# STM32.net
KiCad netlist of a schematic drawn in Altium Designer
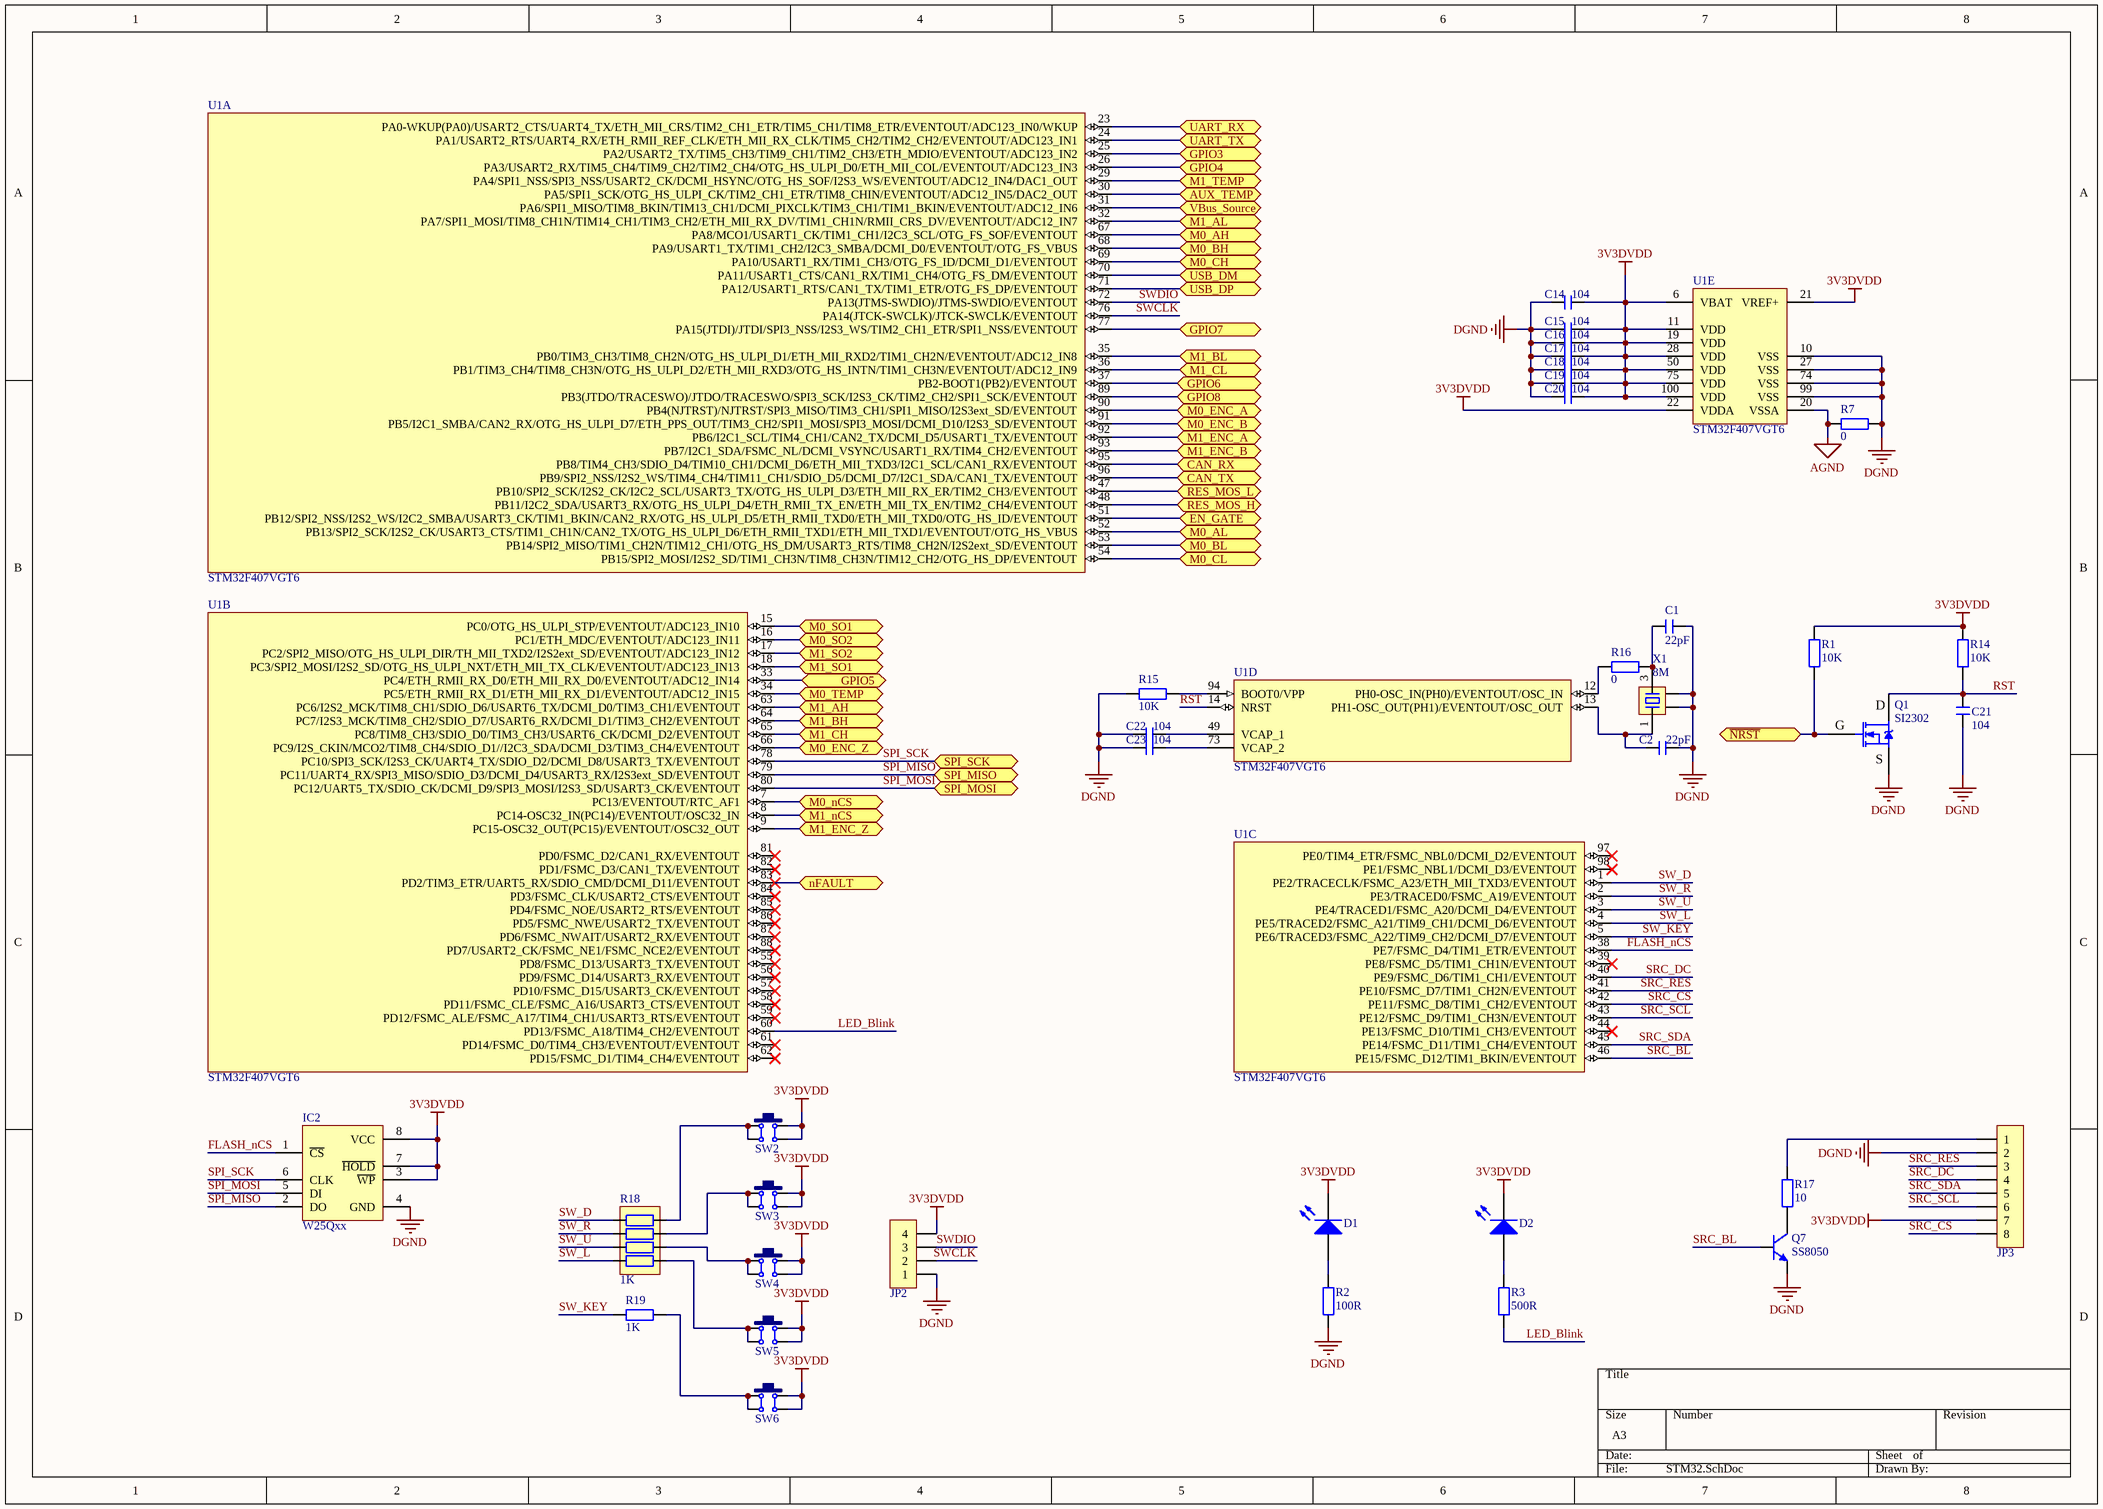
[diagram p0: STM32.SchDoc]

(export (version "E")
  (design (tool "Eeschema 10.0.6"))
  (components
    (comp (ref "C1")
      (value "22pF")
      (footprint "C 0603_L")
      (description "贴片电容")
      (libsource (lib "0.1 - 电阻-电容-电感") (part "C"))
    )
    (comp (ref "C2")
      (value "22pF")
      (footprint "C 0603_L")
      (description "贴片电容")
      (libsource (lib "0.1 - 电阻-电容-电感") (part "C"))
    )
    (comp (ref "C14")
      (value "104")
      (footprint "C 0603_L")
      (description "贴片电容")
      (libsource (lib "0.1 - 电阻-电容-电感") (part "C"))
    )
    (comp (ref "C15")
      (value "104")
      (footprint "C 0603_L")
      (description "贴片电容")
      (libsource (lib "0.1 - 电阻-电容-电感") (part "C"))
    )
    (comp (ref "C16")
      (value "104")
      (footprint "C 0603_L")
      (description "贴片电容")
      (libsource (lib "0.1 - 电阻-电容-电感") (part "C"))
    )
    (comp (ref "C17")
      (value "104")
      (footprint "C 0603_L")
      (description "贴片电容")
      (libsource (lib "0.1 - 电阻-电容-电感") (part "C"))
    )
    (comp (ref "C18")
      (value "104")
      (footprint "C 0603_L")
      (description "贴片电容")
      (libsource (lib "0.1 - 电阻-电容-电感") (part "C"))
    )
    (comp (ref "C19")
      (value "104")
      (footprint "C 0603_L")
      (description "贴片电容")
      (libsource (lib "0.1 - 电阻-电容-电感") (part "C"))
    )
    (comp (ref "C20")
      (value "104")
      (footprint "C 0603_L")
      (description "贴片电容")
      (libsource (lib "0.1 - 电阻-电容-电感") (part "C"))
    )
    (comp (ref "C21")
      (value "104")
      (footprint "C 0603_L")
      (description "贴片电容")
      (libsource (lib "0.1 - 电阻-电容-电感") (part "C"))
    )
    (comp (ref "C22")
      (value "104")
      (footprint "C 0603_L")
      (description "贴片电容")
      (libsource (lib "0.1 - 电阻-电容-电感") (part "C"))
    )
    (comp (ref "C23")
      (value "104")
      (footprint "C 0603_L")
      (description "贴片电容")
      (libsource (lib "0.1 - 电阻-电容-电感") (part "C"))
    )
    (comp (ref "D1")
      (value "LED")
      (footprint "LED 0603W")
      (description "发光二极管")
      (libsource (lib "0.3 - LED发光二极管") (part "LED"))
    )
    (comp (ref "D2")
      (value "LED")
      (footprint "LED 0603W")
      (description "发光二极管")
      (libsource (lib "0.3 - LED发光二极管") (part "LED"))
    )
    (comp (ref "IC2")
      (value "W25Qxx")
      (footprint "SOP8W_N")
      (description "SPI Flash")
      (fields (field (name "版权归属") "封装库来自淘宝 ID：黄晶宝石"))
      (libsource (lib "1.0 - 常见芯片") (part "W25Q"))
    )
    (comp (ref "JP2")
      (value "HDR-1X4")
      (footprint "HDR2.54-LI-4P")
      (description "4P接插件")
      (fields (field (name "版权归属") "封装库来自淘宝 ID：黄晶宝石"))
      (libsource (lib "5.3 - 接插件-脚距2.54 (100mil) ") (part "Header 4"))
    )
    (comp (ref "JP3")
      (value "HDR-1X8")
      (footprint "FPC0.5 2H-WS-8P")
      (description "8P接插件")
      (fields (field (name "版权归属") "封装库来自淘宝 ID：黄晶宝石"))
      (libsource (lib "5.0 - 接插件-脚距1.25") (part "Header 8"))
    )
    (comp (ref "Q1")
      (value "SI2302")
      (footprint "SOT23-3N")
      (description "N沟道场效应管")
      (libsource (lib "0.5 - 场效应管-可控硅") (part "SI2302"))
    )
    (comp (ref "Q7")
      (value "SS8050")
      (footprint "SOT23-3N")
      (description "高频放大-NPN型")
      (fields (field (name "版权归属") "封装库来自淘宝 ID：黄晶宝石"))
      (libsource (lib "0.4 - 三极管") (part "8050-SMD"))
    )
    (comp (ref "R1")
      (value "10K")
      (footprint "R 0603_L")
      (description "贴片电阻")
      (fields (field (name "版权归属") "来自淘宝 ID：黄晶宝石"))
      (libsource (lib "0.1 - 电阻-电容-电感") (part "R"))
    )
    (comp (ref "R2")
      (value "100R")
      (footprint "R 0603_L")
      (description "贴片电阻")
      (fields (field (name "版权归属") "来自淘宝 ID：黄晶宝石"))
      (libsource (lib "0.1 - 电阻-电容-电感") (part "R"))
    )
    (comp (ref "R3")
      (value "500R")
      (footprint "R 0603_L")
      (description "贴片电阻")
      (fields (field (name "版权归属") "来自淘宝 ID：黄晶宝石"))
      (libsource (lib "0.1 - 电阻-电容-电感") (part "R"))
    )
    (comp (ref "R7")
      (value "0")
      (footprint "R 0603_L")
      (description "贴片电阻")
      (fields (field (name "版权归属") "来自淘宝 ID：黄晶宝石"))
      (libsource (lib "0.1 - 电阻-电容-电感") (part "R"))
    )
    (comp (ref "R14")
      (value "10K")
      (footprint "R 0603_L")
      (description "贴片电阻")
      (fields (field (name "版权归属") "来自淘宝 ID：黄晶宝石"))
      (libsource (lib "0.1 - 电阻-电容-电感") (part "R"))
    )
    (comp (ref "R15")
      (value "10K")
      (footprint "R 0603_L")
      (description "贴片电阻")
      (fields (field (name "版权归属") "来自淘宝 ID：黄晶宝石"))
      (libsource (lib "0.1 - 电阻-电容-电感") (part "R"))
    )
    (comp (ref "R16")
      (value "0")
      (footprint "R 0603_L")
      (description "贴片电阻")
      (fields (field (name "版权归属") "来自淘宝 ID：黄晶宝石"))
      (libsource (lib "0.1 - 电阻-电容-电感") (part "R"))
    )
    (comp (ref "R17")
      (value "10")
      (footprint "R 0603_L")
      (description "贴片电阻")
      (fields (field (name "版权归属") "来自淘宝 ID：黄晶宝石"))
      (libsource (lib "0.1 - 电阻-电容-电感") (part "R"))
    )
    (comp (ref "R18")
      (value "1K")
      (footprint "RCA-8P4R-0603")
      (description "贴片排阻")
      (fields (field (name "版权归属") "封装库来自淘宝 ID：黄晶宝石"))
      (libsource (lib "0.1 - 电阻-电容-电感") (part "R-8P4R"))
    )
    (comp (ref "R19")
      (value "1K")
      (footprint "R 0603_L")
      (description "贴片电阻")
      (fields (field (name "版权归属") "来自淘宝 ID：黄晶宝石"))
      (libsource (lib "0.1 - 电阻-电容-电感") (part "R"))
    )
    (comp (ref "SW2")
      (value "6x6x5")
      (footprint "TSW SMD-6*6*4.3")
      (description "贴片6x6轻触开关")
      (fields (field (name "版权归属") "封装库来自淘宝 ID：黄晶宝石"))
      (libsource (lib "0.7 - 常用按键-开关") (part "TSW SMD-6x6"))
    )
    (comp (ref "SW3")
      (value "6x6x5")
      (footprint "TSW SMD-6*6*4.3")
      (description "贴片6x6轻触开关")
      (fields (field (name "版权归属") "封装库来自淘宝 ID：黄晶宝石"))
      (libsource (lib "0.7 - 常用按键-开关") (part "TSW SMD-6x6"))
    )
    (comp (ref "SW4")
      (value "6x6x5")
      (footprint "TSW SMD-6*6*4.3")
      (description "贴片6x6轻触开关")
      (fields (field (name "版权归属") "封装库来自淘宝 ID：黄晶宝石"))
      (libsource (lib "0.7 - 常用按键-开关") (part "TSW SMD-6x6"))
    )
    (comp (ref "SW5")
      (value "6x6x5")
      (footprint "TSW SMD-6*6*4.3")
      (description "贴片6x6轻触开关")
      (fields (field (name "版权归属") "封装库来自淘宝 ID：黄晶宝石"))
      (libsource (lib "0.7 - 常用按键-开关") (part "TSW SMD-6x6"))
    )
    (comp (ref "SW6")
      (value "6x6x5")
      (footprint "TSW SMD-6*6*4.3")
      (description "贴片6x6轻触开关")
      (fields (field (name "版权归属") "封装库来自淘宝 ID：黄晶宝石"))
      (libsource (lib "0.7 - 常用按键-开关") (part "TSW SMD-6x6"))
    )
    (comp (ref "U1")
      (value "STM32F407VGT6")
      (footprint "LQFP100_V")
      (libsource (lib "2.5 - STM32 F4系列MCU 集成库") (part "STM32F407VGT6"))
    )
    (comp (ref "X1")
      (value "8M")
      (footprint "OSC 3225-4P")
      (description "4脚无源晶振")
      (fields (field (name "版权归属") "封装库来自淘宝卖家 ID：黄晶宝石"))
      (libsource (lib "2.0 - 保险丝-晶振-光耦") (part "XTAL-4P"))
    )
  )
  (nets
    (net (code "1") (name "/AUX_TEMP") (class "Default")
      (node (ref "U1") (pin "30") (pinfunction "PA5/SPI1_SCK/OTG_HS_ULPI_CK/TIM2_CH1_ETR/TIM8_CHIN/EVENTOUT/ADC12_IN5/DAC2_OUT_30") (pintype "bidirectional"))
    )
    (net (code "2") (name "/CAN_RX") (class "Default")
      (node (ref "U1") (pin "95") (pinfunction "PB8/TIM4_CH3/SDIO_D4/TIM10_CH1/DCMI_D6/ETH_MII_TXD3/I2C1_SCL/CAN1_RX/EVENTOUT_95") (pintype "bidirectional"))
    )
    (net (code "3") (name "/CAN_TX") (class "Default")
      (node (ref "U1") (pin "96") (pinfunction "PB9/SPI2_NSS/I2S2_WS/TIM4_CH4/TIM11_CH1/SDIO_D5/DCMI_D7/I2C1_SDA/CAN1_TX/EVENTOUT_96") (pintype "bidirectional"))
    )
    (net (code "4") (name "/EN_GATE") (class "Default")
      (node (ref "U1") (pin "51") (pinfunction "PB12/SPI2_NSS/I2S2_WS/I2C2_SMBA/USART3_CK/TIM1_BKIN/CAN2_RX/OTG_HS_ULPI_D5/ETH_RMII_TXD0/ETH_MII_TXD0/OTG_HS_ID/EVENTOUT_51") (pintype "bidirectional"))
    )
    (net (code "5") (name "/FLASH_nCS") (class "Default")
      (node (ref "IC2") (pin "1") (pinfunction "~{CS}_1") (pintype "passive"))
      (node (ref "U1") (pin "38") (pinfunction "PE7/FSMC_D4/TIM1_ETR/EVENTOUT_38") (pintype "bidirectional"))
    )
    (net (code "6") (name "/GPIO3") (class "Default")
      (node (ref "U1") (pin "25") (pinfunction "PA2/USART2_TX/TIM5_CH3/TIM9_CH1/TIM2_CH3/ETH_MDIO/EVENTOUT/ADC123_IN2_25") (pintype "bidirectional"))
    )
    (net (code "7") (name "/GPIO4") (class "Default")
      (node (ref "U1") (pin "26") (pinfunction "PA3/USART2_RX/TIM5_CH4/TIM9_CH2/TIM2_CH4/OTG_HS_ULPI_D0/ETH_MII_COL/EVENTOUT/ADC123_IN3_26") (pintype "bidirectional"))
    )
    (net (code "8") (name "/GPIO5") (class "Default")
      (node (ref "U1") (pin "33") (pinfunction "PC4/ETH_RMII_RX_D0/ETH_MII_RX_D0/EVENTOUT/ADC12_IN14_33") (pintype "bidirectional"))
    )
    (net (code "9") (name "/GPIO6") (class "Default")
      (node (ref "U1") (pin "37") (pinfunction "PB2-BOOT1(PB2)/EVENTOUT_37") (pintype "bidirectional"))
    )
    (net (code "10") (name "/GPIO7") (class "Default")
      (node (ref "U1") (pin "77") (pinfunction "PA15(JTDI)/JTDI/SPI3_NSS/I2S3_WS/TIM2_CH1_ETR/SPI1_NSS/EVENTOUT_77") (pintype "bidirectional"))
    )
    (net (code "11") (name "/GPIO8") (class "Default")
      (node (ref "U1") (pin "89") (pinfunction "PB3(JTDO/TRACESWO)/JTDO/TRACESWO/SPI3_SCK/I2S3_CK/TIM2_CH2/SPI1_SCK/EVENTOUT_89") (pintype "bidirectional"))
    )
    (net (code "12") (name "/LED_Blink") (class "Default")
      (node (ref "R3") (pin "1") (pinfunction "1_1") (pintype "passive"))
      (node (ref "U1") (pin "60") (pinfunction "PD13/FSMC_A18/TIM4_CH2/EVENTOUT_60") (pintype "bidirectional"))
    )
    (net (code "13") (name "/M0_AH") (class "Default")
      (node (ref "U1") (pin "67") (pinfunction "PA8/MCO1/USART1_CK/TIM1_CH1/I2C3_SCL/OTG_FS_SOF/EVENTOUT_67") (pintype "bidirectional"))
    )
    (net (code "14") (name "/M0_AL") (class "Default")
      (node (ref "U1") (pin "52") (pinfunction "PB13/SPI2_SCK/I2S2_CK/USART3_CTS/TIM1_CH1N/CAN2_TX/OTG_HS_ULPI_D6/ETH_RMII_TXD1/ETH_MII_TXD1/EVENTOUT/OTG_HS_VBUS_52") (pintype "bidirectional"))
    )
    (net (code "15") (name "/M0_BH") (class "Default")
      (node (ref "U1") (pin "68") (pinfunction "PA9/USART1_TX/TIM1_CH2/I2C3_SMBA/DCMI_D0/EVENTOUT/OTG_FS_VBUS_68") (pintype "bidirectional"))
    )
    (net (code "16") (name "/M0_BL") (class "Default")
      (node (ref "U1") (pin "53") (pinfunction "PB14/SPI2_MISO/TIM1_CH2N/TIM12_CH1/OTG_HS_DM/USART3_RTS/TIM8_CH2N/I2S2ext_SD/EVENTOUT_53") (pintype "bidirectional"))
    )
    (net (code "17") (name "/M0_CH") (class "Default")
      (node (ref "U1") (pin "69") (pinfunction "PA10/USART1_RX/TIM1_CH3/OTG_FS_ID/DCMI_D1/EVENTOUT_69") (pintype "bidirectional"))
    )
    (net (code "18") (name "/M0_CL") (class "Default")
      (node (ref "U1") (pin "54") (pinfunction "PB15/SPI2_MOSI/I2S2_SD/TIM1_CH3N/TIM8_CH3N/TIM12_CH2/OTG_HS_DP/EVENTOUT_54") (pintype "bidirectional"))
    )
    (net (code "19") (name "/M0_ENC_A") (class "Default")
      (node (ref "U1") (pin "90") (pinfunction "PB4(NJTRST)/NJTRST/SPI3_MISO/TIM3_CH1/SPI1_MISO/I2S3ext_SD/EVENTOUT_90") (pintype "bidirectional"))
    )
    (net (code "20") (name "/M0_ENC_B") (class "Default")
      (node (ref "U1") (pin "91") (pinfunction "PB5/I2C1_SMBA/CAN2_RX/OTG_HS_ULPI_D7/ETH_PPS_OUT/TIM3_CH2/SPI1_MOSI/SPI3_MOSI/DCMI_D10/I2S3_SD/EVENTOUT_91") (pintype "bidirectional"))
    )
    (net (code "21") (name "/M0_ENC_Z") (class "Default")
      (node (ref "U1") (pin "66") (pinfunction "PC9/I2S_CKIN/MCO2/TIM8_CH4/SDIO_D1//I2C3_SDA/DCMI_D3/TIM3_CH4/EVENTOUT_66") (pintype "bidirectional"))
    )
    (net (code "22") (name "/M0_SO1") (class "Default")
      (node (ref "U1") (pin "15") (pinfunction "PC0/OTG_HS_ULPI_STP/EVENTOUT/ADC123_IN10_15") (pintype "bidirectional"))
    )
    (net (code "23") (name "/M0_SO2") (class "Default")
      (node (ref "U1") (pin "16") (pinfunction "PC1/ETH_MDC/EVENTOUT/ADC123_IN11_16") (pintype "bidirectional"))
    )
    (net (code "24") (name "/M0_TEMP") (class "Default")
      (node (ref "U1") (pin "34") (pinfunction "PC5/ETH_RMII_RX_D1/ETH_MII_RX_D1/EVENTOUT/ADC12_IN15_34") (pintype "bidirectional"))
    )
    (net (code "25") (name "/M0_nCS") (class "Default")
      (node (ref "U1") (pin "7") (pinfunction "PC13/EVENTOUT/RTC_AF1_7") (pintype "bidirectional"))
    )
    (net (code "26") (name "/M1_AH") (class "Default")
      (node (ref "U1") (pin "63") (pinfunction "PC6/I2S2_MCK/TIM8_CH1/SDIO_D6/USART6_TX/DCMI_D0/TIM3_CH1/EVENTOUT_63") (pintype "bidirectional"))
    )
    (net (code "27") (name "/M1_AL") (class "Default")
      (node (ref "U1") (pin "32") (pinfunction "PA7/SPI1_MOSI/TIM8_CH1N/TIM14_CH1/TIM3_CH2/ETH_MII_RX_DV/TIM1_CH1N/RMII_CRS_DV/EVENTOUT/ADC12_IN7_32") (pintype "bidirectional"))
    )
    (net (code "28") (name "/M1_BH") (class "Default")
      (node (ref "U1") (pin "64") (pinfunction "PC7/I2S3_MCK/TIM8_CH2/SDIO_D7/USART6_RX/DCMI_D1/TIM3_CH2/EVENTOUT_64") (pintype "bidirectional"))
    )
    (net (code "29") (name "/M1_BL") (class "Default")
      (node (ref "U1") (pin "35") (pinfunction "PB0/TIM3_CH3/TIM8_CH2N/OTG_HS_ULPI_D1/ETH_MII_RXD2/TIM1_CH2N/EVENTOUT/ADC12_IN8_35") (pintype "bidirectional"))
    )
    (net (code "30") (name "/M1_CH") (class "Default")
      (node (ref "U1") (pin "65") (pinfunction "PC8/TIM8_CH3/SDIO_D0/TIM3_CH3/USART6_CK/DCMI_D2/EVENTOUT_65") (pintype "bidirectional"))
    )
    (net (code "31") (name "/M1_CL") (class "Default")
      (node (ref "U1") (pin "36") (pinfunction "PB1/TIM3_CH4/TIM8_CH3N/OTG_HS_ULPI_D2/ETH_MII_RXD3/OTG_HS_INTN/TIM1_CH3N/EVENTOUT/ADC12_IN9_36") (pintype "bidirectional"))
    )
    (net (code "32") (name "/M1_ENC_A") (class "Default")
      (node (ref "U1") (pin "92") (pinfunction "PB6/I2C1_SCL/TIM4_CH1/CAN2_TX/DCMI_D5/USART1_TX/EVENTOUT_92") (pintype "bidirectional"))
    )
    (net (code "33") (name "/M1_ENC_B") (class "Default")
      (node (ref "U1") (pin "93") (pinfunction "PB7/I2C1_SDA/FSMC_NL/DCMI_VSYNC/USART1_RX/TIM4_CH2/EVENTOUT_93") (pintype "bidirectional"))
    )
    (net (code "34") (name "/M1_ENC_Z") (class "Default")
      (node (ref "U1") (pin "9") (pinfunction "PC15-OSC32_OUT(PC15)/EVENTOUT/OSC32_OUT_9") (pintype "bidirectional"))
    )
    (net (code "35") (name "/M1_SO1") (class "Default")
      (node (ref "U1") (pin "18") (pinfunction "PC3/SPI2_MOSI/I2S2_SD/OTG_HS_ULPI_NXT/ETH_MII_TX_CLK/EVENTOUT/ADC123_IN13_18") (pintype "bidirectional"))
    )
    (net (code "36") (name "/M1_SO2") (class "Default")
      (node (ref "U1") (pin "17") (pinfunction "PC2/SPI2_MISO/OTG_HS_ULPI_DIR/TH_MII_TXD2/I2S2ext_SD/EVENTOUT/ADC123_IN12_17") (pintype "bidirectional"))
    )
    (net (code "37") (name "/M1_TEMP") (class "Default")
      (node (ref "U1") (pin "29") (pinfunction "PA4/SPI1_NSS/SPI3_NSS/USART2_CK/DCMI_HSYNC/OTG_HS_SOF/I2S3_WS/EVENTOUT/ADC12_IN4/DAC1_OUT_29") (pintype "bidirectional"))
    )
    (net (code "38") (name "/M1_nCS") (class "Default")
      (node (ref "U1") (pin "8") (pinfunction "PC14-OSC32_IN(PC14)/EVENTOUT/OSC32_IN_8") (pintype "bidirectional"))
    )
    (net (code "39") (name "/RES_MOS_H") (class "Default")
      (node (ref "U1") (pin "48") (pinfunction "PB11/I2C2_SDA/USART3_RX/OTG_HS_ULPI_D4/ETH_RMII_TX_EN/ETH_MII_TX_EN/TIM2_CH4/EVENTOUT_48") (pintype "bidirectional"))
    )
    (net (code "40") (name "/RES_MOS_L") (class "Default")
      (node (ref "U1") (pin "47") (pinfunction "PB10/SPI2_SCK/I2S2_CK/I2C2_SCL/USART3_TX/OTG_HS_ULPI_D3/ETH_MII_RX_ER/TIM2_CH3/EVENTOUT_47") (pintype "bidirectional"))
    )
    (net (code "41") (name "/RST") (class "Default")
      (node (ref "C21") (pin "2") (pinfunction "2_2") (pintype "passive"))
      (node (ref "Q1") (pin "3") (pinfunction "D_3") (pintype "passive"))
      (node (ref "R14") (pin "1") (pinfunction "1_1") (pintype "passive"))
      (node (ref "U1") (pin "14") (pinfunction "NRST_14") (pintype "bidirectional"))
    )
    (net (code "42") (name "/SPI_MISO") (class "Default")
      (node (ref "IC2") (pin "2") (pinfunction "DO_2") (pintype "passive"))
      (node (ref "U1") (pin "79") (pinfunction "PC11/UART4_RX/SPI3_MISO/SDIO_D3/DCMI_D4/USART3_RX/I2S3ext_SD/EVENTOUT_79") (pintype "bidirectional"))
    )
    (net (code "43") (name "/SPI_MOSI") (class "Default")
      (node (ref "IC2") (pin "5") (pinfunction "DI_5") (pintype "passive"))
      (node (ref "U1") (pin "80") (pinfunction "PC12/UART5_TX/SDIO_CK/DCMI_D9/SPI3_MOSI/I2S3_SD/USART3_CK/EVENTOUT_80") (pintype "bidirectional"))
    )
    (net (code "44") (name "/SPI_SCK") (class "Default")
      (node (ref "IC2") (pin "6") (pinfunction "CLK_6") (pintype "passive"))
      (node (ref "U1") (pin "78") (pinfunction "PC10/SPI3_SCK/I2S3_CK/UART4_TX/SDIO_D2/DCMI_D8/USART3_TX/EVENTOUT_78") (pintype "bidirectional"))
    )
    (net (code "45") (name "/SRC_BL") (class "Default")
      (node (ref "Q7") (pin "1") (pinfunction "B_1") (pintype "passive"))
      (node (ref "U1") (pin "46") (pinfunction "PE15/FSMC_D12/TIM1_BKIN/EVENTOUT_46") (pintype "bidirectional"))
    )
    (net (code "46") (name "/SRC_CS") (class "Default")
      (node (ref "JP3") (pin "8") (pinfunction "8_8") (pintype "passive"))
      (node (ref "U1") (pin "42") (pinfunction "PE11/FSMC_D8/TIM1_CH2/EVENTOUT_42") (pintype "bidirectional"))
    )
    (net (code "47") (name "/SRC_DC") (class "Default")
      (node (ref "JP3") (pin "4") (pinfunction "4_4") (pintype "passive"))
      (node (ref "U1") (pin "40") (pinfunction "PE9/FSMC_D6/TIM1_CH1/EVENTOUT_40") (pintype "bidirectional"))
    )
    (net (code "48") (name "/SRC_RES") (class "Default")
      (node (ref "JP3") (pin "3") (pinfunction "3_3") (pintype "passive"))
      (node (ref "U1") (pin "41") (pinfunction "PE10/FSMC_D7/TIM1_CH2N/EVENTOUT_41") (pintype "bidirectional"))
    )
    (net (code "49") (name "/SRC_SCL") (class "Default")
      (node (ref "JP3") (pin "6") (pinfunction "6_6") (pintype "passive"))
      (node (ref "U1") (pin "43") (pinfunction "PE12/FSMC_D9/TIM1_CH3N/EVENTOUT_43") (pintype "bidirectional"))
    )
    (net (code "50") (name "/SRC_SDA") (class "Default")
      (node (ref "JP3") (pin "5") (pinfunction "5_5") (pintype "passive"))
      (node (ref "U1") (pin "45") (pinfunction "PE14/FSMC_D11/TIM1_CH4/EVENTOUT_45") (pintype "bidirectional"))
    )
    (net (code "51") (name "/SWCLK") (class "Default")
      (node (ref "JP2") (pin "2") (pinfunction "2_2") (pintype "passive"))
      (node (ref "U1") (pin "76") (pinfunction "PA14(JTCK-SWCLK)/JTCK-SWCLK/EVENTOUT_76") (pintype "bidirectional"))
    )
    (net (code "52") (name "/SWDIO") (class "Default")
      (node (ref "JP2") (pin "3") (pinfunction "3_3") (pintype "passive"))
      (node (ref "U1") (pin "72") (pinfunction "PA13(JTMS-SWDIO)/JTMS-SWDIO/EVENTOUT_72") (pintype "bidirectional"))
    )
    (net (code "53") (name "/SW_D") (class "Default")
      (node (ref "R18") (pin "8") (pinfunction "8_8") (pintype "passive"))
      (node (ref "U1") (pin "1") (pinfunction "PE2/TRACECLK/FSMC_A23/ETH_MII_TXD3/EVENTOUT_1") (pintype "bidirectional"))
    )
    (net (code "54") (name "/SW_KEY") (class "Default")
      (node (ref "R19") (pin "2") (pinfunction "2_2") (pintype "passive"))
      (node (ref "U1") (pin "5") (pinfunction "PE6/TRACED3/FSMC_A22/TIM9_CH2/DCMI_D7/EVENTOUT_5") (pintype "bidirectional"))
    )
    (net (code "55") (name "/SW_L") (class "Default")
      (node (ref "R18") (pin "5") (pinfunction "5_5") (pintype "passive"))
      (node (ref "U1") (pin "4") (pinfunction "PE5/TRACED2/FSMC_A21/TIM9_CH1/DCMI_D6/EVENTOUT_4") (pintype "bidirectional"))
    )
    (net (code "56") (name "/SW_R") (class "Default")
      (node (ref "R18") (pin "7") (pinfunction "7_7") (pintype "passive"))
      (node (ref "U1") (pin "2") (pinfunction "PE3/TRACED0/FSMC_A19/EVENTOUT_2") (pintype "bidirectional"))
    )
    (net (code "57") (name "/SW_U") (class "Default")
      (node (ref "R18") (pin "6") (pinfunction "6_6") (pintype "passive"))
      (node (ref "U1") (pin "3") (pinfunction "PE4/TRACED1/FSMC_A20/DCMI_D4/EVENTOUT_3") (pintype "bidirectional"))
    )
    (net (code "58") (name "/UART_RX") (class "Default")
      (node (ref "U1") (pin "23") (pinfunction "PA0-WKUP(PA0)/USART2_CTS/UART4_TX/ETH_MII_CRS/TIM2_CH1_ETR/TIM5_CH1/TIM8_ETR/EVENTOUT/ADC123_IN0/WKUP_23") (pintype "bidirectional"))
    )
    (net (code "59") (name "/UART_TX") (class "Default")
      (node (ref "U1") (pin "24") (pinfunction "PA1/USART2_RTS/UART4_RX/ETH_RMII_REF_CLK/ETH_MII_RX_CLK/TIM5_CH2/TIM2_CH2/EVENTOUT/ADC123_IN1_24") (pintype "bidirectional"))
    )
    (net (code "60") (name "/USB_DM") (class "Default")
      (node (ref "U1") (pin "70") (pinfunction "PA11/USART1_CTS/CAN1_RX/TIM1_CH4/OTG_FS_DM/EVENTOUT_70") (pintype "bidirectional"))
    )
    (net (code "61") (name "/USB_DP") (class "Default")
      (node (ref "U1") (pin "71") (pinfunction "PA12/USART1_RTS/CAN1_TX/TIM1_ETR/OTG_FS_DP/EVENTOUT_71") (pintype "bidirectional"))
    )
    (net (code "62") (name "/VBus_Source") (class "Default")
      (node (ref "U1") (pin "31") (pinfunction "PA6/SPI1_MISO/TIM8_BKIN/TIM13_CH1/DCMI_PIXCLK/TIM3_CH1/TIM1_BKIN/EVENTOUT/ADC12_IN6_31") (pintype "bidirectional"))
    )
    (net (code "63") (name "/nFAULT") (class "Default")
      (node (ref "U1") (pin "83") (pinfunction "PD2/TIM3_ETR/UART5_RX/SDIO_CMD/DCMI_D11/EVENTOUT_83") (pintype "bidirectional+no_connect"))
    )
    (net (code "64") (name "/~{NRST}") (class "Default")
      (node (ref "Q1") (pin "1") (pinfunction "G_1") (pintype "passive"))
      (node (ref "R1") (pin "1") (pinfunction "1_1") (pintype "passive"))
    )
    (net (code "65") (name "3V3DVDD") (class "Default")
      (node (ref "C14") (pin "2") (pinfunction "2_2") (pintype "passive"))
      (node (ref "C15") (pin "2") (pinfunction "2_2") (pintype "passive"))
      (node (ref "C16") (pin "2") (pinfunction "2_2") (pintype "passive"))
      (node (ref "C17") (pin "2") (pinfunction "2_2") (pintype "passive"))
      (node (ref "C18") (pin "2") (pinfunction "2_2") (pintype "passive"))
      (node (ref "C19") (pin "2") (pinfunction "2_2") (pintype "passive"))
      (node (ref "C20") (pin "2") (pinfunction "2_2") (pintype "passive"))
      (node (ref "D1") (pin "2") (pinfunction "K_2") (pintype "passive"))
      (node (ref "D2") (pin "2") (pinfunction "K_2") (pintype "passive"))
      (node (ref "IC2") (pin "3") (pinfunction "~{WP}_3") (pintype "passive"))
      (node (ref "IC2") (pin "7") (pinfunction "~{HOLD}_7") (pintype "passive"))
      (node (ref "IC2") (pin "8") (pinfunction "VCC_8") (pintype "passive"))
      (node (ref "JP2") (pin "4") (pinfunction "4_4") (pintype "passive"))
      (node (ref "JP3") (pin "7") (pinfunction "7_7") (pintype "passive"))
      (node (ref "R1") (pin "2") (pinfunction "2_2") (pintype "passive"))
      (node (ref "R14") (pin "2") (pinfunction "2_2") (pintype "passive"))
      (node (ref "SW2") (pin "2") (pinfunction "2_2") (pintype "passive"))
      (node (ref "SW2") (pin "3") (pinfunction "3_3") (pintype "passive"))
      (node (ref "SW3") (pin "2") (pinfunction "2_2") (pintype "passive"))
      (node (ref "SW3") (pin "3") (pinfunction "3_3") (pintype "passive"))
      (node (ref "SW4") (pin "2") (pinfunction "2_2") (pintype "passive"))
      (node (ref "SW4") (pin "3") (pinfunction "3_3") (pintype "passive"))
      (node (ref "SW5") (pin "2") (pinfunction "2_2") (pintype "passive"))
      (node (ref "SW5") (pin "3") (pinfunction "3_3") (pintype "passive"))
      (node (ref "SW6") (pin "2") (pinfunction "2_2") (pintype "passive"))
      (node (ref "SW6") (pin "3") (pinfunction "3_3") (pintype "passive"))
      (node (ref "U1") (pin "100") (pinfunction "VDD_100") (pintype "power_in"))
      (node (ref "U1") (pin "11") (pinfunction "VDD_11") (pintype "power_in"))
      (node (ref "U1") (pin "19") (pinfunction "VDD_19") (pintype "power_in"))
      (node (ref "U1") (pin "21") (pinfunction "VREF+_21") (pintype "power_in"))
      (node (ref "U1") (pin "22") (pinfunction "VDDA_22") (pintype "power_in"))
      (node (ref "U1") (pin "28") (pinfunction "VDD_28") (pintype "power_in"))
      (node (ref "U1") (pin "50") (pinfunction "VDD_50") (pintype "power_in"))
      (node (ref "U1") (pin "6") (pinfunction "VBAT_6") (pintype "power_in"))
      (node (ref "U1") (pin "75") (pinfunction "VDD_75") (pintype "power_in"))
    )
    (net (code "66") (name "AGND") (class "Default")
      (node (ref "R7") (pin "2") (pinfunction "2_2") (pintype "passive"))
      (node (ref "U1") (pin "20") (pinfunction "VSSA_20") (pintype "power_in"))
    )
    (net (code "67") (name "DGND") (class "Default")
      (node (ref "C1") (pin "1") (pinfunction "1_1") (pintype "passive"))
      (node (ref "C14") (pin "1") (pinfunction "1_1") (pintype "passive"))
      (node (ref "C15") (pin "1") (pinfunction "1_1") (pintype "passive"))
      (node (ref "C16") (pin "1") (pinfunction "1_1") (pintype "passive"))
      (node (ref "C17") (pin "1") (pinfunction "1_1") (pintype "passive"))
      (node (ref "C18") (pin "1") (pinfunction "1_1") (pintype "passive"))
      (node (ref "C19") (pin "1") (pinfunction "1_1") (pintype "passive"))
      (node (ref "C2") (pin "2") (pinfunction "2_2") (pintype "passive"))
      (node (ref "C20") (pin "1") (pinfunction "1_1") (pintype "passive"))
      (node (ref "C21") (pin "1") (pinfunction "1_1") (pintype "passive"))
      (node (ref "C22") (pin "1") (pinfunction "1_1") (pintype "passive"))
      (node (ref "C23") (pin "1") (pinfunction "1_1") (pintype "passive"))
      (node (ref "IC2") (pin "4") (pinfunction "GND_4") (pintype "passive"))
      (node (ref "JP2") (pin "1") (pinfunction "1_1") (pintype "passive"))
      (node (ref "JP3") (pin "2") (pinfunction "2_2") (pintype "passive"))
      (node (ref "Q1") (pin "2") (pinfunction "S_2") (pintype "passive"))
      (node (ref "Q7") (pin "2") (pinfunction "E_2") (pintype "passive"))
      (node (ref "R15") (pin "1") (pinfunction "1_1") (pintype "passive"))
      (node (ref "R2") (pin "1") (pinfunction "1_1") (pintype "passive"))
      (node (ref "R7") (pin "1") (pinfunction "1_1") (pintype "passive"))
      (node (ref "U1") (pin "10") (pinfunction "VSS_10") (pintype "power_in"))
      (node (ref "U1") (pin "27") (pinfunction "VSS_27") (pintype "power_in"))
      (node (ref "U1") (pin "74") (pinfunction "VSS_74") (pintype "power_in"))
      (node (ref "U1") (pin "99") (pinfunction "VSS_99") (pintype "power_in"))
      (node (ref "X1") (pin "2") (pinfunction "2_2") (pintype "passive"))
      (node (ref "X1") (pin "4") (pinfunction "4_4") (pintype "passive"))
    )
    (net (code "68") (name "Net-(C1-Pad2)") (class "Default")
      (node (ref "C1") (pin "2") (pinfunction "2_2") (pintype "passive"))
      (node (ref "R16") (pin "1") (pinfunction "1_1") (pintype "passive"))
      (node (ref "X1") (pin "3") (pinfunction "3_3") (pintype "passive"))
    )
    (net (code "69") (name "Net-(D1-A)") (class "Default")
      (node (ref "D1") (pin "1") (pinfunction "A_1") (pintype "passive"))
      (node (ref "R2") (pin "2") (pinfunction "2_2") (pintype "passive"))
    )
    (net (code "70") (name "Net-(D2-A)") (class "Default")
      (node (ref "D2") (pin "1") (pinfunction "A_1") (pintype "passive"))
      (node (ref "R3") (pin "2") (pinfunction "2_2") (pintype "passive"))
    )
    (net (code "71") (name "Net-(JP3-Pad1)") (class "Default")
      (node (ref "JP3") (pin "1") (pinfunction "1_1") (pintype "passive"))
      (node (ref "R17") (pin "2") (pinfunction "2_2") (pintype "passive"))
    )
    (net (code "72") (name "Net-(Q7-C)") (class "Default")
      (node (ref "Q7") (pin "3") (pinfunction "C_3") (pintype "passive"))
      (node (ref "R17") (pin "1") (pinfunction "1_1") (pintype "passive"))
    )
    (net (code "73") (name "Net-(R18-Pad1)") (class "Default")
      (node (ref "R18") (pin "1") (pinfunction "1_1") (pintype "passive"))
      (node (ref "SW2") (pin "1") (pinfunction "1_1") (pintype "passive"))
      (node (ref "SW2") (pin "4") (pinfunction "4_4") (pintype "passive"))
    )
    (net (code "74") (name "Net-(R18-Pad2)") (class "Default")
      (node (ref "R18") (pin "2") (pinfunction "2_2") (pintype "passive"))
      (node (ref "SW3") (pin "1") (pinfunction "1_1") (pintype "passive"))
      (node (ref "SW3") (pin "4") (pinfunction "4_4") (pintype "passive"))
    )
    (net (code "75") (name "Net-(R18-Pad3)") (class "Default")
      (node (ref "R18") (pin "3") (pinfunction "3_3") (pintype "passive"))
      (node (ref "SW4") (pin "1") (pinfunction "1_1") (pintype "passive"))
      (node (ref "SW4") (pin "4") (pinfunction "4_4") (pintype "passive"))
    )
    (net (code "76") (name "Net-(R18-Pad4)") (class "Default")
      (node (ref "R18") (pin "4") (pinfunction "4_4") (pintype "passive"))
      (node (ref "SW5") (pin "1") (pinfunction "1_1") (pintype "passive"))
      (node (ref "SW5") (pin "4") (pinfunction "4_4") (pintype "passive"))
    )
    (net (code "77") (name "Net-(R19-Pad1)") (class "Default")
      (node (ref "R19") (pin "1") (pinfunction "1_1") (pintype "passive"))
      (node (ref "SW6") (pin "1") (pinfunction "1_1") (pintype "passive"))
      (node (ref "SW6") (pin "4") (pinfunction "4_4") (pintype "passive"))
    )
    (net (code "78") (name "Net-(U1D-BOOT0{slash}VPP)") (class "Default")
      (node (ref "R15") (pin "2") (pinfunction "2_2") (pintype "passive"))
      (node (ref "U1") (pin "94") (pinfunction "BOOT0/VPP_94") (pintype "input"))
    )
    (net (code "79") (name "Net-(U1D-PH0-OSC_IN(PH0){slash}EVENTOUT{slash}OSC_IN)") (class "Default")
      (node (ref "R16") (pin "2") (pinfunction "2_2") (pintype "passive"))
      (node (ref "U1") (pin "12") (pinfunction "PH0-OSC_IN(PH0)/EVENTOUT/OSC_IN_12") (pintype "bidirectional"))
    )
    (net (code "80") (name "Net-(U1D-PH1-OSC_OUT(PH1){slash}EVENTOUT{slash}OSC_OUT)") (class "Default")
      (node (ref "C2") (pin "1") (pinfunction "1_1") (pintype "passive"))
      (node (ref "U1") (pin "13") (pinfunction "PH1-OSC_OUT(PH1)/EVENTOUT/OSC_OUT_13") (pintype "bidirectional"))
      (node (ref "X1") (pin "1") (pinfunction "1_1") (pintype "passive"))
    )
    (net (code "81") (name "Net-(U1D-VCAP_1)") (class "Default")
      (node (ref "C22") (pin "2") (pinfunction "2_2") (pintype "passive"))
      (node (ref "U1") (pin "49") (pinfunction "VCAP_1_49") (pintype "power_in"))
    )
    (net (code "82") (name "Net-(U1D-VCAP_2)") (class "Default")
      (node (ref "C23") (pin "2") (pinfunction "2_2") (pintype "passive"))
      (node (ref "U1") (pin "73") (pinfunction "VCAP_2_73") (pintype "power_in"))
    )
    (net (code "83") (name "unconnected-(U1B-PD0{slash}FSMC_D2{slash}CAN1_RX{slash}EVENTOUT-Pad81)") (class "Default")
      (node (ref "U1") (pin "81") (pinfunction "PD0/FSMC_D2/CAN1_RX/EVENTOUT_81") (pintype "bidirectional+no_connect"))
    )
    (net (code "84") (name "unconnected-(U1B-PD1{slash}FSMC_D3{slash}CAN1_TX{slash}EVENTOUT-Pad82)") (class "Default")
      (node (ref "U1") (pin "82") (pinfunction "PD1/FSMC_D3/CAN1_TX/EVENTOUT_82") (pintype "bidirectional+no_connect"))
    )
    (net (code "85") (name "unconnected-(U1B-PD3{slash}FSMC_CLK{slash}USART2_CTS{slash}EVENTOUT-Pad84)") (class "Default")
      (node (ref "U1") (pin "84") (pinfunction "PD3/FSMC_CLK/USART2_CTS/EVENTOUT_84") (pintype "bidirectional+no_connect"))
    )
    (net (code "86") (name "unconnected-(U1B-PD4{slash}FSMC_NOE{slash}USART2_RTS{slash}EVENTOUT-Pad85)") (class "Default")
      (node (ref "U1") (pin "85") (pinfunction "PD4/FSMC_NOE/USART2_RTS/EVENTOUT_85") (pintype "bidirectional+no_connect"))
    )
    (net (code "87") (name "unconnected-(U1B-PD5{slash}FSMC_NWE{slash}USART2_TX{slash}EVENTOUT-Pad86)") (class "Default")
      (node (ref "U1") (pin "86") (pinfunction "PD5/FSMC_NWE/USART2_TX/EVENTOUT_86") (pintype "bidirectional+no_connect"))
    )
    (net (code "88") (name "unconnected-(U1B-PD6{slash}FSMC_NWAIT{slash}USART2_RX{slash}EVENTOUT-Pad87)") (class "Default")
      (node (ref "U1") (pin "87") (pinfunction "PD6/FSMC_NWAIT/USART2_RX/EVENTOUT_87") (pintype "bidirectional+no_connect"))
    )
    (net (code "89") (name "unconnected-(U1B-PD7{slash}USART2_CK{slash}FSMC_NE1{slash}FSMC_NCE2{slash}EVENTOUT-Pad88)") (class "Default")
      (node (ref "U1") (pin "88") (pinfunction "PD7/USART2_CK/FSMC_NE1/FSMC_NCE2/EVENTOUT_88") (pintype "bidirectional+no_connect"))
    )
    (net (code "90") (name "unconnected-(U1B-PD8{slash}FSMC_D13{slash}USART3_TX{slash}EVENTOUT-Pad55)") (class "Default")
      (node (ref "U1") (pin "55") (pinfunction "PD8/FSMC_D13/USART3_TX/EVENTOUT_55") (pintype "bidirectional+no_connect"))
    )
    (net (code "91") (name "unconnected-(U1B-PD9{slash}FSMC_D14{slash}USART3_RX{slash}EVENTOUT-Pad56)") (class "Default")
      (node (ref "U1") (pin "56") (pinfunction "PD9/FSMC_D14/USART3_RX/EVENTOUT_56") (pintype "bidirectional+no_connect"))
    )
    (net (code "92") (name "unconnected-(U1B-PD10{slash}FSMC_D15{slash}USART3_CK{slash}EVENTOUT-Pad57)") (class "Default")
      (node (ref "U1") (pin "57") (pinfunction "PD10/FSMC_D15/USART3_CK/EVENTOUT_57") (pintype "bidirectional+no_connect"))
    )
    (net (code "93") (name "unconnected-(U1B-PD11{slash}FSMC_CLE{slash}FSMC_A16{slash}USART3_CTS{slash}EVENTOUT-Pad58)") (class "Default")
      (node (ref "U1") (pin "58") (pinfunction "PD11/FSMC_CLE/FSMC_A16/USART3_CTS/EVENTOUT_58") (pintype "bidirectional+no_connect"))
    )
    (net (code "94") (name "unconnected-(U1B-PD12{slash}FSMC_ALE{slash}FSMC_A17{slash}TIM4_CH1{slash}USART3_RTS{slash}EVENTOUT-Pad59)") (class "Default")
      (node (ref "U1") (pin "59") (pinfunction "PD12/FSMC_ALE/FSMC_A17/TIM4_CH1/USART3_RTS/EVENTOUT_59") (pintype "bidirectional+no_connect"))
    )
    (net (code "95") (name "unconnected-(U1B-PD14{slash}FSMC_D0{slash}TIM4_CH3{slash}EVENTOUT{slash}EVENTOUT-Pad61)") (class "Default")
      (node (ref "U1") (pin "61") (pinfunction "PD14/FSMC_D0/TIM4_CH3/EVENTOUT/EVENTOUT_61") (pintype "bidirectional+no_connect"))
    )
    (net (code "96") (name "unconnected-(U1B-PD15{slash}FSMC_D1{slash}TIM4_CH4{slash}EVENTOUT-Pad62)") (class "Default")
      (node (ref "U1") (pin "62") (pinfunction "PD15/FSMC_D1/TIM4_CH4/EVENTOUT_62") (pintype "bidirectional+no_connect"))
    )
    (net (code "97") (name "unconnected-(U1C-PE0{slash}TIM4_ETR{slash}FSMC_NBL0{slash}DCMI_D2{slash}EVENTOUT-Pad97)") (class "Default")
      (node (ref "U1") (pin "97") (pinfunction "PE0/TIM4_ETR/FSMC_NBL0/DCMI_D2/EVENTOUT_97") (pintype "bidirectional+no_connect"))
    )
    (net (code "98") (name "unconnected-(U1C-PE1{slash}FSMC_NBL1{slash}DCMI_D3{slash}EVENTOUT-Pad98)") (class "Default")
      (node (ref "U1") (pin "98") (pinfunction "PE1/FSMC_NBL1/DCMI_D3/EVENTOUT_98") (pintype "bidirectional+no_connect"))
    )
    (net (code "99") (name "unconnected-(U1C-PE8{slash}FSMC_D5{slash}TIM1_CH1N{slash}EVENTOUT-Pad39)") (class "Default")
      (node (ref "U1") (pin "39") (pinfunction "PE8/FSMC_D5/TIM1_CH1N/EVENTOUT_39") (pintype "bidirectional+no_connect"))
    )
    (net (code "100") (name "unconnected-(U1C-PE13{slash}FSMC_D10{slash}TIM1_CH3{slash}EVENTOUT-Pad44)") (class "Default")
      (node (ref "U1") (pin "44") (pinfunction "PE13/FSMC_D10/TIM1_CH3/EVENTOUT_44") (pintype "bidirectional+no_connect"))
    )
  )
)
